# Battery.net
KiCad netlist of a schematic drawn in Altium Designer
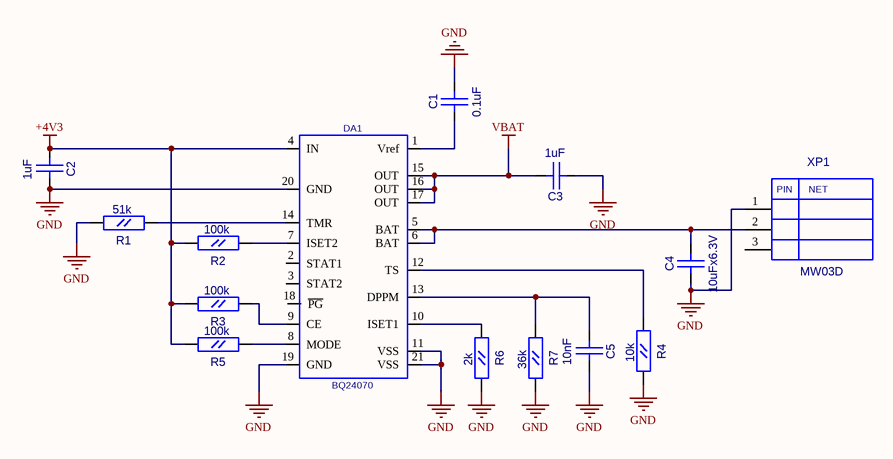
[diagram p0: Battery.SchDoc]

(export (version "E")
  (design (tool "Eeschema 10.0.6"))
  (components
    (comp (ref "C1")
      (value "0.1uF")
      (footprint "CC0603")
      (description "CC0603")
      (libsource (lib "gprs_modem_2") (part "CC0603"))
    )
    (comp (ref "C2")
      (value "1uF")
      (footprint "CC0603")
      (description "CC0603")
      (libsource (lib "gprs_modem_2") (part "CC0603"))
    )
    (comp (ref "C3")
      (value "1uF")
      (footprint "CC0603")
      (description "CC0603")
      (libsource (lib "gprs_modem_2") (part "CC0603"))
    )
    (comp (ref "C4")
      (value "10uFx6.3V")
      (footprint "CC0805")
      (description "CC0805")
      (libsource (lib "gprs_modem_2") (part "CC0805"))
    )
    (comp (ref "C5")
      (value "10nF")
      (footprint "CC0603")
      (description "CC0603")
      (libsource (lib "gprs_modem_2") (part "CC0603"))
    )
    (comp (ref "DA1")
      (value "BQ24070")
      (footprint "P-PQFP-N20")
      (libsource (lib "gprs_modem") (part "BQ24070"))
    )
    (comp (ref "R1")
      (value "51k")
      (footprint "RC0603")
      (description "RC0603")
      (libsource (lib "gprs_modem_2") (part "RC0603"))
    )
    (comp (ref "R2")
      (value "100k")
      (footprint "RC0603")
      (description "RC0603")
      (libsource (lib "gprs_modem_2") (part "RC0603"))
    )
    (comp (ref "R3")
      (value "100k")
      (footprint "RC0603")
      (description "RC0603")
      (libsource (lib "gprs_modem_2") (part "RC0603"))
    )
    (comp (ref "R4")
      (value "10k")
      (footprint "RC0603")
      (description "RC0603")
      (libsource (lib "gprs_modem_2") (part "RC0603"))
    )
    (comp (ref "R5")
      (value "100k")
      (footprint "RC0603")
      (description "RC0603")
      (libsource (lib "gprs_modem_2") (part "RC0603"))
    )
    (comp (ref "R6")
      (value "2k")
      (footprint "RC0603")
      (description "RC0603")
      (libsource (lib "gprs_modem_2") (part "RC0603"))
    )
    (comp (ref "R7")
      (value "36k")
      (footprint "RC0603")
      (description "RC0603")
      (libsource (lib "gprs_modem_2") (part "RC0603"))
    )
    (comp (ref "XP1") (value "MW03D") (footprint "MW03D") (libsource (lib "gprs_modem") (part "MW03D")))
  )
  (nets
    (net (code "1") (name "+4V3") (class "Default")
      (node (ref "C2") (pin "1") (pinfunction "A_1") (pintype "passive"))
      (node (ref "DA1") (pin "4") (pinfunction "IN_4") (pintype "passive"))
      (node (ref "R2") (pin "2") (pinfunction "B_2") (pintype "passive"))
      (node (ref "R3") (pin "2") (pinfunction "B_2") (pintype "passive"))
      (node (ref "R5") (pin "2") (pinfunction "B_2") (pintype "passive"))
    )
    (net (code "2") (name "GND") (class "Default")
      (node (ref "C1") (pin "2") (pinfunction "B_2") (pintype "passive"))
      (node (ref "C2") (pin "2") (pinfunction "B_2") (pintype "passive"))
      (node (ref "C3") (pin "1") (pinfunction "A_1") (pintype "passive"))
      (node (ref "C4") (pin "1") (pinfunction "A_1") (pintype "passive"))
      (node (ref "C5") (pin "2") (pinfunction "B_2") (pintype "passive"))
      (node (ref "DA1") (pin "11") (pinfunction "VSS_11") (pintype "passive"))
      (node (ref "DA1") (pin "19") (pinfunction "GND_19") (pintype "passive"))
      (node (ref "DA1") (pin "20") (pinfunction "GND_20") (pintype "passive"))
      (node (ref "DA1") (pin "21") (pinfunction "VSS_21") (pintype "passive"))
      (node (ref "R1") (pin "2") (pinfunction "B_2") (pintype "passive"))
      (node (ref "R4") (pin "2") (pinfunction "B_2") (pintype "passive"))
      (node (ref "R6") (pin "2") (pinfunction "B_2") (pintype "passive"))
      (node (ref "R7") (pin "2") (pinfunction "B_2") (pintype "passive"))
      (node (ref "XP1") (pin "1") (pinfunction "1_1") (pintype "passive"))
    )
    (net (code "3") (name "Net-(C1-A)") (class "Default")
      (node (ref "C1") (pin "1") (pinfunction "A_1") (pintype "passive"))
      (node (ref "DA1") (pin "1") (pinfunction "Vref_1") (pintype "passive"))
    )
    (net (code "4") (name "Net-(C4-B)") (class "Default")
      (node (ref "C4") (pin "2") (pinfunction "B_2") (pintype "passive"))
      (node (ref "DA1") (pin "5") (pinfunction "BAT_5") (pintype "passive"))
      (node (ref "DA1") (pin "6") (pinfunction "BAT_6") (pintype "passive"))
      (node (ref "XP1") (pin "2") (pinfunction "2_2") (pintype "passive"))
    )
    (net (code "5") (name "Net-(C5-A)") (class "Default")
      (node (ref "C5") (pin "1") (pinfunction "A_1") (pintype "passive"))
      (node (ref "DA1") (pin "13") (pinfunction "DPPM_13") (pintype "passive"))
      (node (ref "R7") (pin "1") (pinfunction "A_1") (pintype "passive"))
    )
    (net (code "6") (name "Net-(DA1-CE)") (class "Default")
      (node (ref "DA1") (pin "9") (pinfunction "CE_9") (pintype "passive"))
      (node (ref "R3") (pin "1") (pinfunction "A_1") (pintype "passive"))
    )
    (net (code "7") (name "Net-(DA1-ISET1)") (class "Default")
      (node (ref "DA1") (pin "10") (pinfunction "ISET1_10") (pintype "passive"))
      (node (ref "R6") (pin "1") (pinfunction "A_1") (pintype "passive"))
    )
    (net (code "8") (name "Net-(DA1-ISET2)") (class "Default")
      (node (ref "DA1") (pin "7") (pinfunction "ISET2_7") (pintype "passive"))
      (node (ref "R2") (pin "1") (pinfunction "A_1") (pintype "passive"))
    )
    (net (code "9") (name "Net-(DA1-MODE)") (class "Default")
      (node (ref "DA1") (pin "8") (pinfunction "MODE_8") (pintype "passive"))
      (node (ref "R5") (pin "1") (pinfunction "A_1") (pintype "passive"))
    )
    (net (code "10") (name "Net-(DA1-TMR)") (class "Default")
      (node (ref "DA1") (pin "14") (pinfunction "TMR_14") (pintype "passive"))
      (node (ref "R1") (pin "1") (pinfunction "A_1") (pintype "passive"))
    )
    (net (code "11") (name "Net-(DA1-TS)") (class "Default")
      (node (ref "DA1") (pin "12") (pinfunction "TS_12") (pintype "passive"))
      (node (ref "R4") (pin "1") (pinfunction "A_1") (pintype "passive"))
    )
    (net (code "12") (name "VBAT") (class "Default")
      (node (ref "C3") (pin "2") (pinfunction "B_2") (pintype "passive"))
      (node (ref "DA1") (pin "15") (pinfunction "OUT_15") (pintype "passive"))
      (node (ref "DA1") (pin "16") (pinfunction "OUT_16") (pintype "passive"))
      (node (ref "DA1") (pin "17") (pinfunction "OUT_17") (pintype "passive"))
    )
    (net (code "13") (name "unconnected-(DA1-STAT1-Pad2)") (class "Default")
      (node (ref "DA1") (pin "2") (pinfunction "STAT1_2") (pintype "passive"))
    )
    (net (code "14") (name "unconnected-(DA1-STAT2-Pad3)") (class "Default")
      (node (ref "DA1") (pin "3") (pinfunction "STAT2_3") (pintype "passive"))
    )
    (net (code "15") (name "unconnected-(DA1-~{PG}-Pad18)") (class "Default")
      (node (ref "DA1") (pin "18") (pinfunction "~{PG}_18") (pintype "passive"))
    )
    (net (code "16") (name "unconnected-(XP1-Pad3)") (class "Default")
      (node (ref "XP1") (pin "3") (pinfunction "3_3") (pintype "passive"))
    )
  )
)
